# lightboard-215.net
KiCad netlist of a schematic drawn in EAGLE
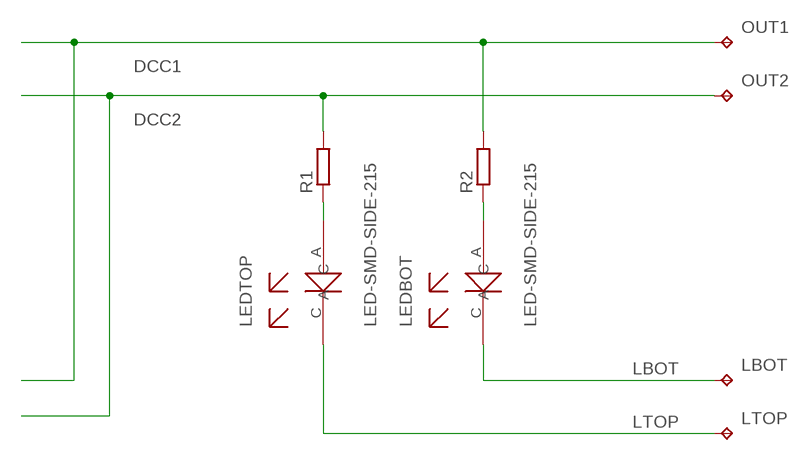
[diagram p0: schematic, sheet 1]

(export (version "E")
  (design (tool "Eeschema 10.0.6"))
  (components
    (comp (ref "LBOT")
      (value "TPB1,27")
      (footprint "eagle-import:B1,27")
      (libsource (lib "eagle-import") (part "TPB1,27"))
    )
    (comp (ref "LEDBOT")
      (value "LED-SMD-SIDE-215")
      (footprint "eagle-import:LED-SMD-SIDE-215")
      (libsource (lib "eagle-import") (part "LED-SMD-SIDE-215"))
    )
    (comp (ref "LEDTOP")
      (value "LED-SMD-SIDE-215")
      (footprint "eagle-import:LED-SMD-SIDE-215")
      (libsource (lib "eagle-import") (part "LED-SMD-SIDE-215"))
    )
    (comp (ref "LTOP")
      (value "TPB1,27")
      (footprint "eagle-import:B1,27")
      (libsource (lib "eagle-import") (part "TPB1,27"))
    )
    (comp (ref "OUT1")
      (value "TPB1,27")
      (footprint "eagle-import:B1,27")
      (libsource (lib "eagle-import") (part "TPB1,27"))
    )
    (comp (ref "OUT2")
      (value "TPB1,27")
      (footprint "eagle-import:B1,27")
      (libsource (lib "eagle-import") (part "TPB1,27"))
    )
    (comp (ref "R1")
      (value "R-EU_R0805")
      (footprint "eagle-import:R0805")
      (libsource (lib "eagle-import") (part "R-EU_R0805"))
    )
    (comp (ref "R2")
      (value "R-EU_R0805")
      (footprint "eagle-import:R0805")
      (libsource (lib "eagle-import") (part "R-EU_R0805"))
    )
  )
  (nets
    (net (code "1") (name "/DCC1") (class "Default")
      (node (ref "OUT1") (pin "TP") (pinfunction "TP_TP") (pintype "input"))
      (node (ref "R2") (pin "2") (pinfunction "2_2") (pintype "passive"))
    )
    (net (code "2") (name "/DCC2") (class "Default")
      (node (ref "OUT2") (pin "TP") (pinfunction "TP_TP") (pintype "input"))
      (node (ref "R1") (pin "2") (pinfunction "2_2") (pintype "passive"))
    )
    (net (code "3") (name "/LBOT") (class "Default")
      (node (ref "LBOT") (pin "TP") (pinfunction "TP_TP") (pintype "input"))
      (node (ref "LEDBOT") (pin "C") (pinfunction "C_C") (pintype "bidirectional"))
    )
    (net (code "4") (name "/LTOP") (class "Default")
      (node (ref "LEDTOP") (pin "C") (pinfunction "C_C") (pintype "bidirectional"))
      (node (ref "LTOP") (pin "TP") (pinfunction "TP_TP") (pintype "input"))
    )
    (net (code "5") (name "Net-(LEDBOT-PadA)") (class "Default")
      (node (ref "LEDBOT") (pin "A") (pinfunction "A_A") (pintype "bidirectional"))
      (node (ref "R2") (pin "1") (pinfunction "1_1") (pintype "passive"))
    )
    (net (code "6") (name "Net-(LEDTOP-PadA)") (class "Default")
      (node (ref "LEDTOP") (pin "A") (pinfunction "A_A") (pintype "bidirectional"))
      (node (ref "R1") (pin "1") (pinfunction "1_1") (pintype "passive"))
    )
  )
)
